# BQ25504v4.net
KiCad netlist of a schematic drawn in Altium Designer
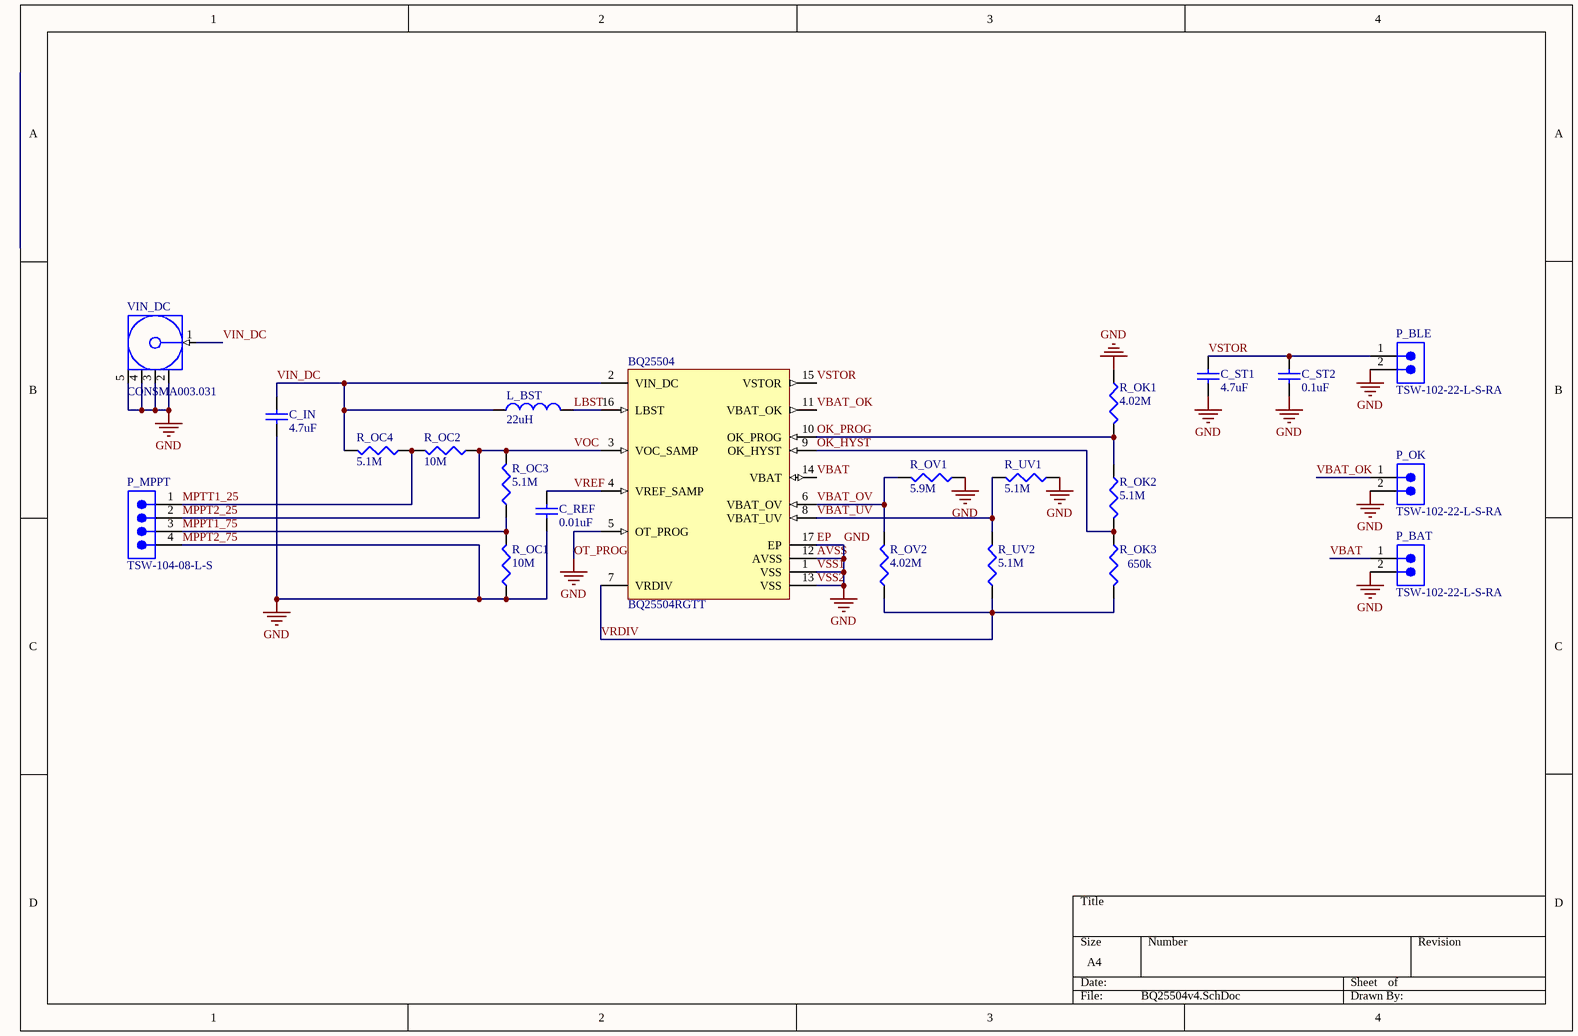
[diagram p0: BQ25504v4.SchDoc]

(export (version "E")
  (design (tool "Eeschema 10.0.6"))
  (components
    (comp (ref "BQ25504")
      (value "BQ25504RGTT")
      (footprint "RGT0016C_V")
      (fields (field (name "MANUFACTURER") "Texas Instruments"))
      (libsource (lib "Altium Content Vault") (part "TI-BQ25504RGT16-1700X1700TP"))
    )
    (comp (ref "C_IN")
      (value "4.7uF")
      (footprint "C0805")
      (description "Capacitor (Semiconductor SIM Model)")
      (fields (field (name "Comment") "Cap Semi") (field (name "PUBLISHER") "Altium Limited"))
      (libsource (lib "Miscellaneous Devices") (part "Cap Semi"))
    )
    (comp (ref "C_REF")
      (value "0.01uF")
      (footprint "1608[0603]")
      (description "Capacitor (Semiconductor SIM Model)")
      (fields (field (name "Comment") "Cap Semi") (field (name "PUBLISHER") "Altium Limited"))
      (libsource (lib "Miscellaneous Devices") (part "Cap Semi"))
    )
    (comp (ref "C_ST1")
      (value "4.7uF")
      (footprint "C0805")
      (description "Capacitor (Semiconductor SIM Model)")
      (fields (field (name "Comment") "Cap Semi") (field (name "PUBLISHER") "Altium Limited"))
      (libsource (lib "Miscellaneous Devices") (part "Cap Semi"))
    )
    (comp (ref "C_ST2")
      (value "0.1uF")
      (footprint "1608[0603]")
      (description "Capacitor (Semiconductor SIM Model)")
      (fields (field (name "Comment") "Cap Semi") (field (name "PUBLISHER") "Altium Limited"))
      (libsource (lib "Miscellaneous Devices") (part "Cap Semi"))
    )
    (comp (ref "L_BST")
      (value "22uH")
      (footprint "LPS4018")
      (description "Inductor")
      (fields (field (name "PUBLISHER") "Altium Limited"))
      (libsource (lib "Miscellaneous Devices") (part "Inductor"))
    )
    (comp (ref "P_BAT")
      (value "TSW-102-22-L-S-RA")
      (footprint "SMTC-TSW-102-22-X-S-RA")
      (fields (field (name "MANUFACTURER") "Samtec"))
      (libsource (lib "Altium Content Vault") (part "SMTC-TSW-102-X-X-S-X"))
    )
    (comp (ref "P_BLE")
      (value "TSW-102-22-L-S-RA")
      (footprint "SMTC-TSW-102-22-X-S-RA")
      (fields (field (name "MANUFACTURER") "Samtec"))
      (libsource (lib "Altium Content Vault") (part "SMTC-TSW-102-X-X-S-X"))
    )
    (comp (ref "P_MPPT")
      (value "TSW-104-08-L-S")
      (footprint "SMTC-TSW-104-08-X-S")
      (description "0.025\" SQ Post Header, Through-hole, Vertical, -55 to 125 degC, 2.54 mm Pitch, 4-Pin, Male, RoHS")
      (fields (field (name "MANUFACTURER") "Samtec"))
      (libsource (lib "Altium Content Vault") (part "SMTC-TSW-104-08-X-S"))
    )
    (comp (ref "P_OK")
      (value "TSW-102-22-L-S-RA")
      (footprint "SMTC-TSW-102-22-X-S-RA")
      (fields (field (name "MANUFACTURER") "Samtec"))
      (libsource (lib "Altium Content Vault") (part "SMTC-TSW-102-X-X-S-X"))
    )
    (comp (ref "R_OC1")
      (value "10M")
      (footprint "6-0805_N")
      (description "Resistor")
      (fields (field (name "Comment") "Res3") (field (name "PUBLISHER") "Altium Limited"))
      (libsource (lib "Miscellaneous Devices") (part "Res3"))
    )
    (comp (ref "R_OC2")
      (value "10M")
      (footprint "6-0805_N")
      (description "Resistor")
      (fields (field (name "Comment") "Res3") (field (name "PUBLISHER") "Altium Limited"))
      (libsource (lib "Miscellaneous Devices") (part "Res3"))
    )
    (comp (ref "R_OC3")
      (value "5.1M")
      (footprint "J1-0603")
      (description "Resistor")
      (fields (field (name "Comment") "Res3") (field (name "PUBLISHER") "Altium Limited"))
      (libsource (lib "Miscellaneous Devices") (part "Res3"))
    )
    (comp (ref "R_OC4")
      (value "5.1M")
      (footprint "J1-0603")
      (description "Resistor")
      (fields (field (name "Comment") "Res3") (field (name "PUBLISHER") "Altium Limited"))
      (libsource (lib "Miscellaneous Devices") (part "Res3"))
    )
    (comp (ref "R_OK1")
      (value "4.02M")
      (footprint "6-0805_N")
      (description "Resistor")
      (fields (field (name "Comment") "Res3") (field (name "PUBLISHER") "Altium Limited"))
      (libsource (lib "Miscellaneous Devices") (part "Res3"))
    )
    (comp (ref "R_OK2")
      (value "5.1M")
      (footprint "J1-0603")
      (description "Resistor")
      (fields (field (name "Comment") "Res3") (field (name "PUBLISHER") "Altium Limited"))
      (libsource (lib "Miscellaneous Devices") (part "Res3"))
    )
    (comp (ref "R_OK3")
      (value "650k")
      (footprint "J1-0603")
      (description "Resistor")
      (fields (field (name "Comment") "Res3") (field (name "PUBLISHER") "Altium Limited"))
      (libsource (lib "Miscellaneous Devices") (part "Res3"))
    )
    (comp (ref "R_OV1")
      (value "5.9M")
      (footprint "6-0805_N")
      (description "Resistor")
      (fields (field (name "Comment") "Res3") (field (name "PUBLISHER") "Altium Limited"))
      (libsource (lib "Miscellaneous Devices") (part "Res3"))
    )
    (comp (ref "R_OV2")
      (value "4.02M")
      (footprint "6-0805_N")
      (description "Resistor")
      (fields (field (name "Comment") "Res3") (field (name "PUBLISHER") "Altium Limited"))
      (libsource (lib "Miscellaneous Devices") (part "Res3"))
    )
    (comp (ref "R_UV1")
      (value "5.1M")
      (footprint "J1-0603")
      (description "Resistor")
      (fields (field (name "Comment") "Res3") (field (name "PUBLISHER") "Altium Limited"))
      (libsource (lib "Miscellaneous Devices") (part "Res3"))
    )
    (comp (ref "R_UV2")
      (value "5.1M")
      (footprint "J1-0603")
      (description "Resistor")
      (fields (field (name "Comment") "Res3") (field (name "PUBLISHER") "Altium Limited"))
      (libsource (lib "Miscellaneous Devices") (part "Res3"))
    )
    (comp (ref "VIN_DC")
      (value "CONSMA003.031")
      (footprint "CON-SMA-EDGE031")
      (description "SMA Female Edge Mount Connector for 0.031\" Thick Board")
      (libsource (lib "Altium Content Vault") (part "CN-1P-F-RF5"))
    )
  )
  (nets
    (net (code "1") (name "/LBST") (class "Default")
      (node (ref "BQ25504") (pin "16") (pinfunction "LBST_16") (pintype "input"))
      (node (ref "L_BST") (pin "2") (pinfunction "2_2") (pintype "passive"))
    )
    (net (code "2") (name "/MPPT1_75") (class "Default")
      (node (ref "P_MPPT") (pin "3") (pinfunction "3_3") (pintype "passive"))
      (node (ref "R_OC1") (pin "2") (pinfunction "2_2") (pintype "passive"))
      (node (ref "R_OC3") (pin "1") (pinfunction "1_1") (pintype "passive"))
    )
    (net (code "3") (name "/MPPT2_25") (class "Default")
      (node (ref "BQ25504") (pin "3") (pinfunction "VOC_SAMP_3") (pintype "input"))
      (node (ref "P_MPPT") (pin "2") (pinfunction "2_2") (pintype "passive"))
      (node (ref "R_OC2") (pin "1") (pinfunction "1_1") (pintype "passive"))
      (node (ref "R_OC3") (pin "2") (pinfunction "2_2") (pintype "passive"))
    )
    (net (code "4") (name "/MPTT1_25") (class "Default")
      (node (ref "P_MPPT") (pin "1") (pinfunction "1_1") (pintype "passive"))
      (node (ref "R_OC2") (pin "2") (pinfunction "2_2") (pintype "passive"))
      (node (ref "R_OC4") (pin "1") (pinfunction "1_1") (pintype "passive"))
    )
    (net (code "5") (name "/OK_HYST") (class "Default")
      (node (ref "BQ25504") (pin "9") (pinfunction "OK_HYST_9") (pintype "input"))
      (node (ref "R_OK2") (pin "2") (pinfunction "2_2") (pintype "passive"))
      (node (ref "R_OK3") (pin "1") (pinfunction "1_1") (pintype "passive"))
    )
    (net (code "6") (name "/OK_PROG") (class "Default")
      (node (ref "BQ25504") (pin "10") (pinfunction "OK_PROG_10") (pintype "input"))
      (node (ref "R_OK1") (pin "2") (pinfunction "2_2") (pintype "passive"))
      (node (ref "R_OK2") (pin "1") (pinfunction "1_1") (pintype "passive"))
    )
    (net (code "7") (name "/VBAT") (class "Default")
      (node (ref "BQ25504") (pin "14") (pinfunction "VBAT_14") (pintype "bidirectional"))
      (node (ref "P_BAT") (pin "1") (pinfunction "1_1") (pintype "passive"))
    )
    (net (code "8") (name "/VBAT_OK") (class "Default")
      (node (ref "BQ25504") (pin "11") (pinfunction "VBAT_OK_11") (pintype "output"))
      (node (ref "P_OK") (pin "1") (pinfunction "1_1") (pintype "passive"))
    )
    (net (code "9") (name "/VBAT_OV") (class "Default")
      (node (ref "BQ25504") (pin "6") (pinfunction "VBAT_OV_6") (pintype "input"))
      (node (ref "R_OV1") (pin "2") (pinfunction "2_2") (pintype "passive"))
      (node (ref "R_OV2") (pin "2") (pinfunction "2_2") (pintype "passive"))
    )
    (net (code "10") (name "/VBAT_UV") (class "Default")
      (node (ref "BQ25504") (pin "8") (pinfunction "VBAT_UV_8") (pintype "input"))
      (node (ref "R_UV1") (pin "2") (pinfunction "2_2") (pintype "passive"))
      (node (ref "R_UV2") (pin "2") (pinfunction "2_2") (pintype "passive"))
    )
    (net (code "11") (name "/VIN_DC") (class "Default")
      (node (ref "BQ25504") (pin "2") (pinfunction "VIN_DC_2") (pintype "power_in"))
      (node (ref "C_IN") (pin "2") (pinfunction "2_2") (pintype "passive"))
      (node (ref "L_BST") (pin "1") (pinfunction "1_1") (pintype "passive"))
      (node (ref "R_OC4") (pin "2") (pinfunction "2_2") (pintype "passive"))
      (node (ref "VIN_DC") (pin "1") (pinfunction "Signal_1") (pintype "input"))
    )
    (net (code "12") (name "/VRDIV") (class "Default")
      (node (ref "BQ25504") (pin "7") (pinfunction "VRDIV_7") (pintype "power_in"))
      (node (ref "R_OK3") (pin "2") (pinfunction "2_2") (pintype "passive"))
      (node (ref "R_OV2") (pin "1") (pinfunction "1_1") (pintype "passive"))
      (node (ref "R_UV2") (pin "1") (pinfunction "1_1") (pintype "passive"))
    )
    (net (code "13") (name "/VREF") (class "Default")
      (node (ref "BQ25504") (pin "4") (pinfunction "VREF_SAMP_4") (pintype "input"))
      (node (ref "C_REF") (pin "2") (pinfunction "2_2") (pintype "passive"))
    )
    (net (code "14") (name "/VSTOR") (class "Default")
      (node (ref "BQ25504") (pin "15") (pinfunction "VSTOR_15") (pintype "output"))
      (node (ref "C_ST1") (pin "2") (pinfunction "2_2") (pintype "passive"))
      (node (ref "C_ST2") (pin "2") (pinfunction "2_2") (pintype "passive"))
      (node (ref "P_BLE") (pin "1") (pinfunction "1_1") (pintype "passive"))
    )
    (net (code "15") (name "GND") (class "Default")
      (node (ref "BQ25504") (pin "1") (pinfunction "VSS_1") (pintype "power_in"))
      (node (ref "BQ25504") (pin "12") (pinfunction "AVSS_12") (pintype "power_in"))
      (node (ref "BQ25504") (pin "13") (pinfunction "VSS_13") (pintype "power_in"))
      (node (ref "BQ25504") (pin "17") (pinfunction "EP_17") (pintype "passive"))
      (node (ref "BQ25504") (pin "5") (pinfunction "OT_PROG_5") (pintype "input"))
      (node (ref "C_IN") (pin "1") (pinfunction "1_1") (pintype "passive"))
      (node (ref "C_REF") (pin "1") (pinfunction "1_1") (pintype "passive"))
      (node (ref "C_ST1") (pin "1") (pinfunction "1_1") (pintype "passive"))
      (node (ref "C_ST2") (pin "1") (pinfunction "1_1") (pintype "passive"))
      (node (ref "P_BAT") (pin "2") (pinfunction "2_2") (pintype "passive"))
      (node (ref "P_BLE") (pin "2") (pinfunction "2_2") (pintype "passive"))
      (node (ref "P_MPPT") (pin "4") (pinfunction "4_4") (pintype "passive"))
      (node (ref "P_OK") (pin "2") (pinfunction "2_2") (pintype "passive"))
      (node (ref "R_OC1") (pin "1") (pinfunction "1_1") (pintype "passive"))
      (node (ref "R_OK1") (pin "1") (pinfunction "1_1") (pintype "passive"))
      (node (ref "R_OV1") (pin "1") (pinfunction "1_1") (pintype "passive"))
      (node (ref "R_UV1") (pin "1") (pinfunction "1_1") (pintype "passive"))
      (node (ref "VIN_DC") (pin "2") (pinfunction "GND_2") (pintype "power_in"))
      (node (ref "VIN_DC") (pin "3") (pinfunction "GND_3") (pintype "power_in"))
      (node (ref "VIN_DC") (pin "4") (pinfunction "GND_4") (pintype "power_in"))
      (node (ref "VIN_DC") (pin "5") (pinfunction "GND_5") (pintype "power_in"))
    )
  )
)
